# Hydrogen_Rocket_BK.net
KiCad netlist of a schematic drawn in EasyEDA
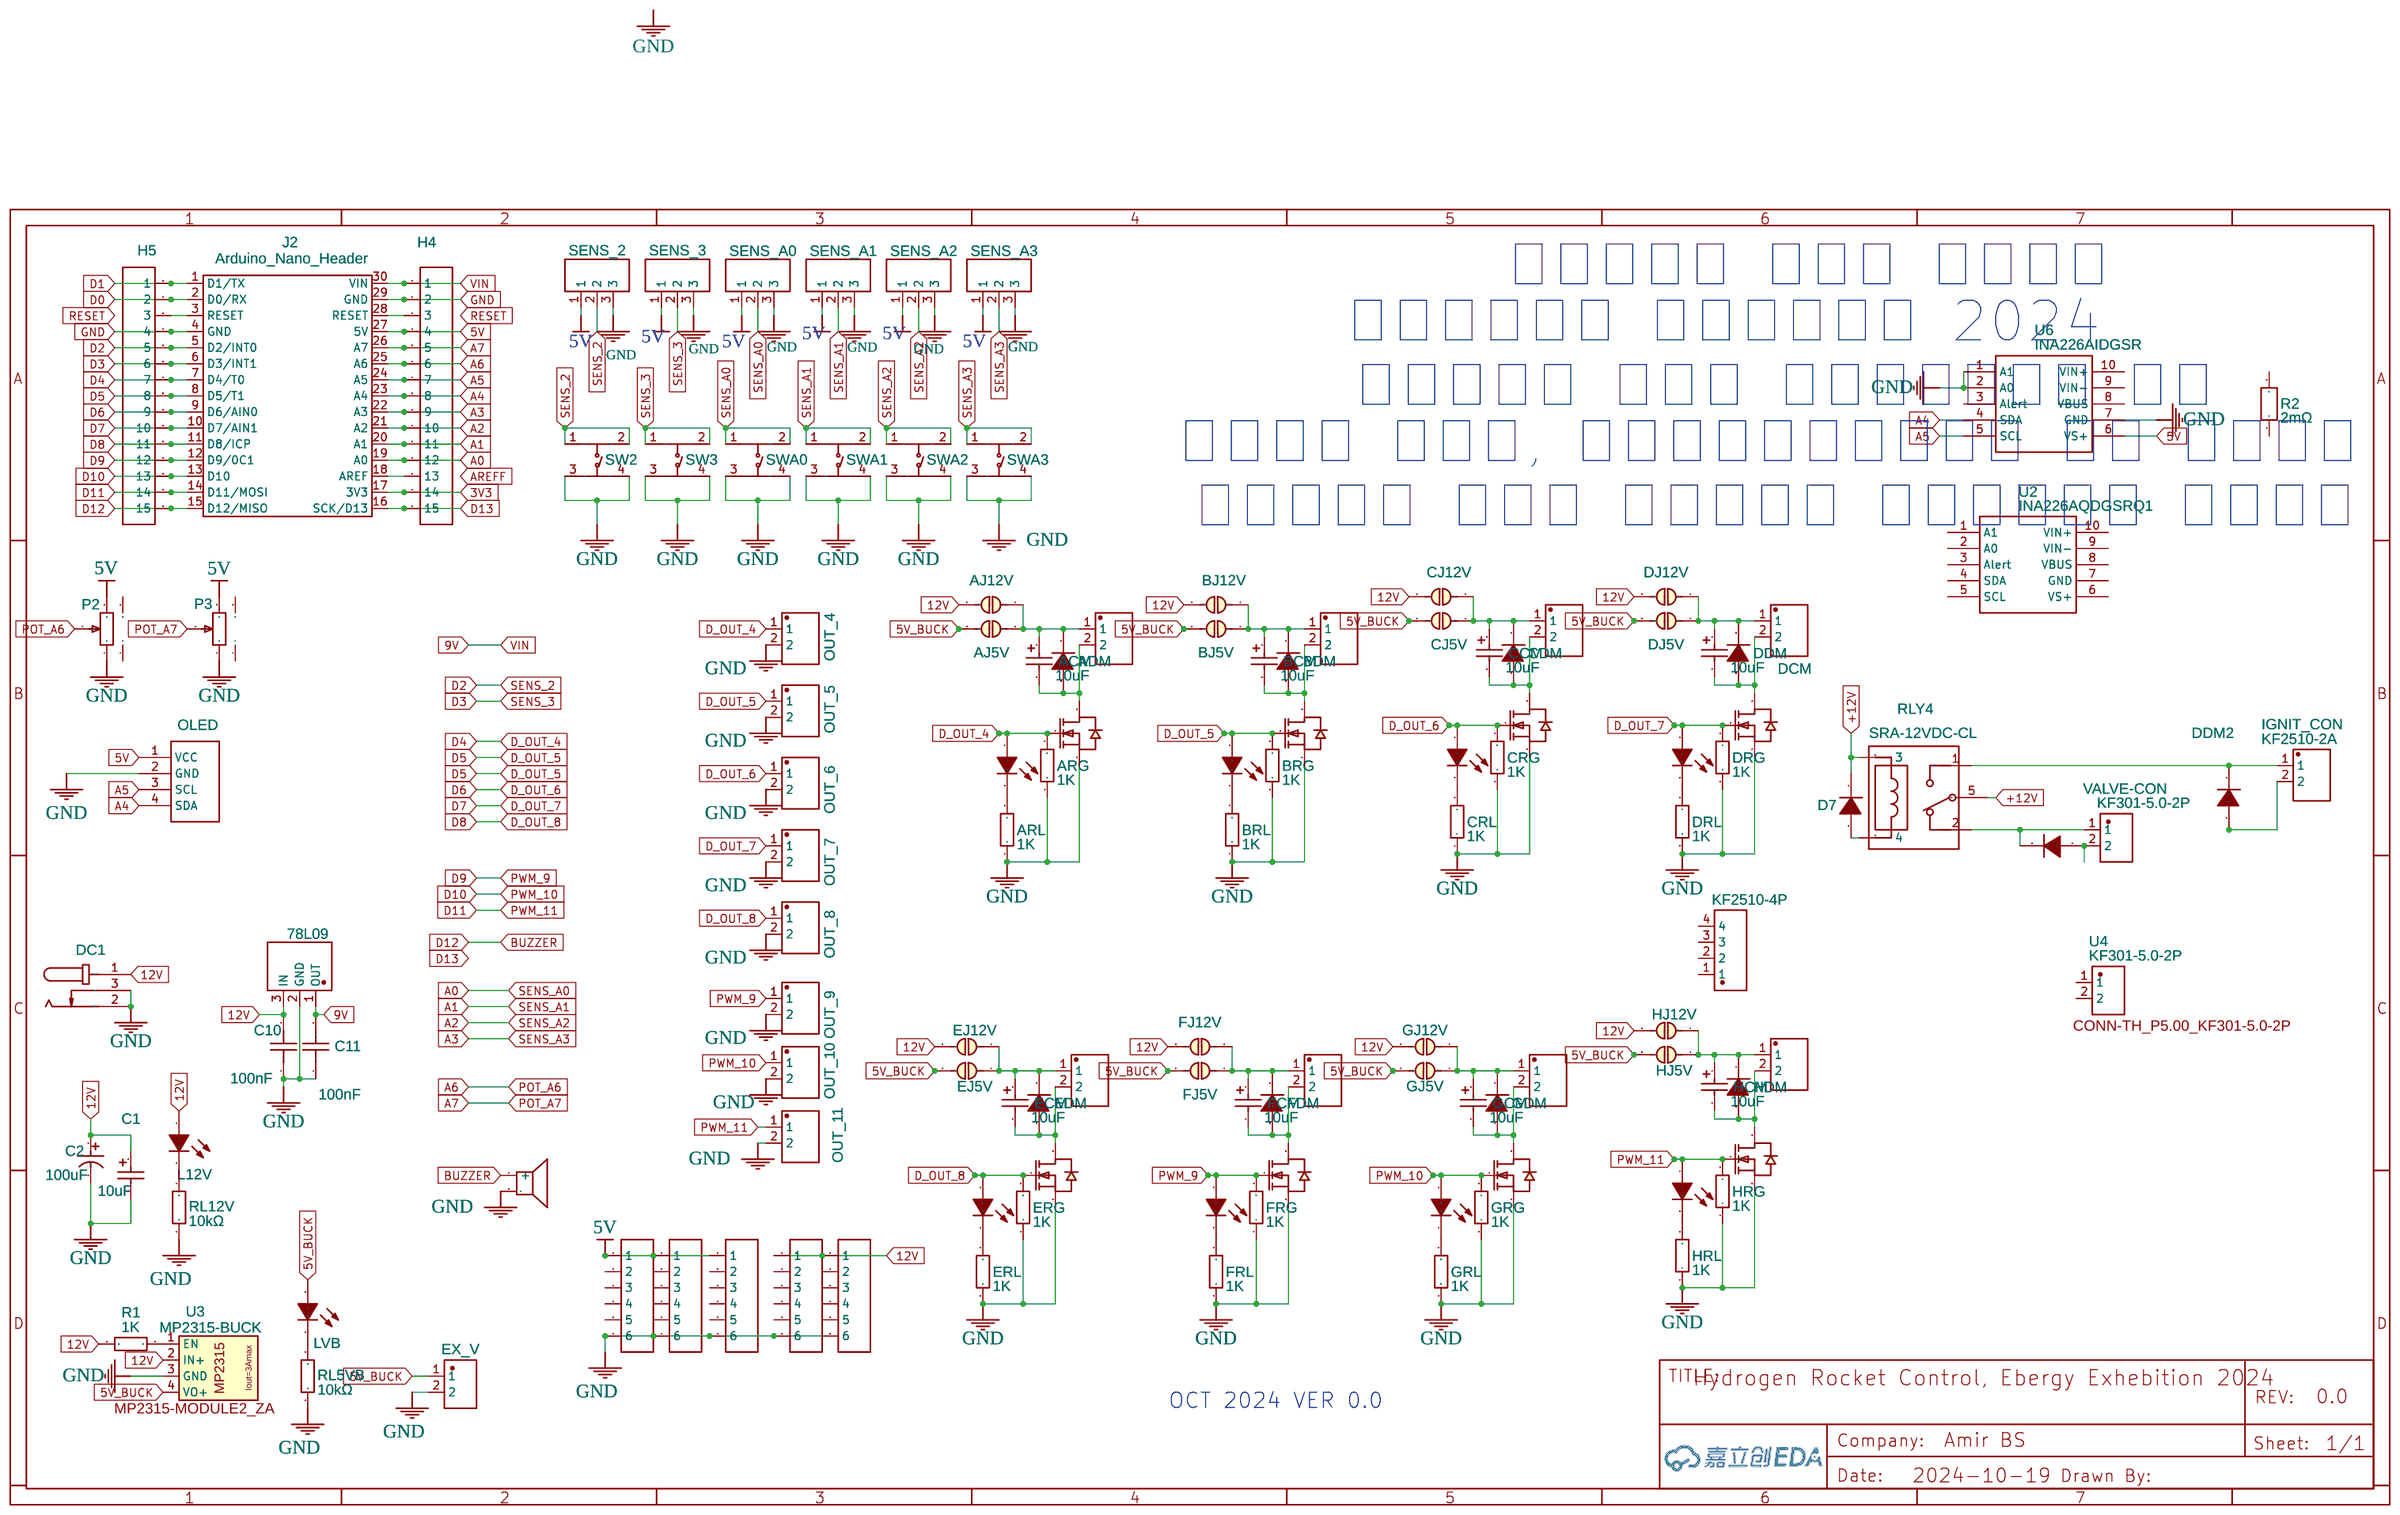
[diagram p0: schematic sheet]

(export (version "E")
  (design (tool "Eeschema 10.0.6"))
  (components
    (comp (ref "ACM") (value "10uF") (libsource (lib "") (part "TAJA106K016RNJ")))
    (comp (ref "ACON")
      (value "KF2510-2A")
      (fields (field (name "Manufacturer") "BOOMELE"))
      (libsource (lib "") (part "KF2510-2A_7"))
    )
    (comp (ref "ADM")
      (value "1N4007")
      (fields (field (name "Manufacturer Part") "1N4007F") (field (name "Manufacturer") "SK"))
      (libsource (lib "") (part "1N4007F_4"))
    )
    (comp (ref "AJ5V") (value "JUMPER-SMT_2") (libsource (lib "") (part "JUMPER-SMT_2_6")))
    (comp (ref "AJ12V") (value "JUMPER-SMT_2") (libsource (lib "") (part "JUMPER-SMT_2_8")))
    (comp (ref "ALD")
      (value "LED")
      (fields
        (field (name "Manufacturer Part") "19-217/BHC-ZL1M2RY/3T")
        (field (name "Manufacturer") "EVERLIGHT")
      )
      (libsource (lib "") (part "19-217/BHC-ZL1M2RY/3T_4"))
    )
    (comp (ref "AQ")
      (value "Q")
      (fields (field (name "Manufacturer Part") "AO3400") (field (name "Manufacturer") "ElecSuper(静芯微）"))
      (libsource (lib "") (part "JSM2302_1"))
    )
    (comp (ref "ARG")
      (value "1K")
      (fields (field (name "Manufacturer Part") "0603WAF1001T5E") (field (name "Manufacturer") "UniOhm"))
      (libsource (lib "") (part "0603WAF1001T5E_5"))
    )
    (comp (ref "ARL")
      (value "1K")
      (fields (field (name "Manufacturer Part") "0603WAF1001T5E") (field (name "Manufacturer") "UniOhm"))
      (libsource (lib "") (part "0603WAF1001T5E_1"))
    )
    (comp (ref "BCM") (value "10uF") (libsource (lib "") (part "TAJA106K016RNJ_1")))
    (comp (ref "BCON")
      (value "KF2510-2A")
      (fields (field (name "Manufacturer") "BOOMELE"))
      (libsource (lib "") (part "KF2510-2A_3"))
    )
    (comp (ref "BDM")
      (value "1N4007")
      (fields (field (name "Manufacturer Part") "1N4007F") (field (name "Manufacturer") "SK"))
      (libsource (lib "") (part "1N4007F_8"))
    )
    (comp (ref "BJ5V") (value "JUMPER-SMT_2") (libsource (lib "") (part "JUMPER-SMT_2_5")))
    (comp (ref "BJ12V") (value "JUMPER-SMT_2") (libsource (lib "") (part "JUMPER-SMT_2_1")))
    (comp (ref "BLD")
      (value "LED")
      (fields
        (field (name "Manufacturer Part") "19-217/BHC-ZL1M2RY/3T")
        (field (name "Manufacturer") "EVERLIGHT")
      )
      (libsource (lib "") (part "19-217/BHC-ZL1M2RY/3T_9"))
    )
    (comp (ref "BQ")
      (value "Q")
      (fields (field (name "Manufacturer Part") "AO3400") (field (name "Manufacturer") "ElecSuper(静芯微）"))
      (libsource (lib "") (part "JSM2302_3"))
    )
    (comp (ref "BRG")
      (value "1K")
      (fields (field (name "Manufacturer Part") "0603WAF1001T5E") (field (name "Manufacturer") "UniOhm"))
      (libsource (lib "") (part "0603WAF1001T5E_11"))
    )
    (comp (ref "BRL")
      (value "1K")
      (fields (field (name "Manufacturer Part") "0603WAF1001T5E") (field (name "Manufacturer") "UniOhm"))
      (libsource (lib "") (part "0603WAF1001T5E_10"))
    )
    (comp (ref "BUZZER1") (value "BUZZER-12X9") (libsource (lib "") (part "BUZZER-12X9")))
    (comp (ref "C1")
      (value "10uF")
      (fields (field (name "Manufacturer") "Kyocera AVX"))
      (libsource (lib "") (part "TAJA106K016RNJ_5"))
    )
    (comp (ref "C2")
      (value "100uF")
      (fields (field (name "Manufacturer") "CX(承兴)"))
      (libsource (lib "") (part "100uF 35V 6.3*11"))
    )
    (comp (ref "C10") (value "100nF") (libsource (lib "") (part "CC0603KRX7R9BB104")))
    (comp (ref "C11") (value "100nF") (libsource (lib "") (part "CC0603KRX7R9BB104")))
    (comp (ref "CCM") (value "10uF") (libsource (lib "") (part "TAJA106K016RNJ_2")))
    (comp (ref "CCON")
      (value "KF2510-2A")
      (fields (field (name "Manufacturer") "BOOMELE"))
      (libsource (lib "") (part "KF2510-2A_6"))
    )
    (comp (ref "CDM")
      (value "1N4007")
      (fields (field (name "Manufacturer Part") "1N4007F") (field (name "Manufacturer") "SK"))
      (libsource (lib "") (part "1N4007F"))
    )
    (comp (ref "CJ5V") (value "JUMPER-SMT_2") (libsource (lib "") (part "JUMPER-SMT_2_14")))
    (comp (ref "CJ12V") (value "JUMPER-SMT_2") (libsource (lib "") (part "JUMPER-SMT_2_9")))
    (comp (ref "CLD")
      (value "LED")
      (fields
        (field (name "Manufacturer Part") "19-217/BHC-ZL1M2RY/3T")
        (field (name "Manufacturer") "EVERLIGHT")
      )
      (libsource (lib "") (part "19-217/BHC-ZL1M2RY/3T_3"))
    )
    (comp (ref "CQ")
      (value "Q")
      (fields (field (name "Manufacturer Part") "AO3400") (field (name "Manufacturer") "ElecSuper(静芯微）"))
      (libsource (lib "") (part "JSM2302_5"))
    )
    (comp (ref "CRG")
      (value "1K")
      (fields (field (name "Manufacturer Part") "0603WAF1001T5E") (field (name "Manufacturer") "UniOhm"))
      (libsource (lib "") (part "0603WAF1001T5E_15"))
    )
    (comp (ref "CRL")
      (value "1K")
      (fields (field (name "Manufacturer Part") "0603WAF1001T5E") (field (name "Manufacturer") "UniOhm"))
      (libsource (lib "") (part "0603WAF1001T5E_12"))
    )
    (comp (ref "D7")
      (value "M7_C95872")
      (fields (field (name "Manufacturer") "MDD"))
      (libsource (lib "") (part "M7_C95872"))
    )
    (comp (ref "DC1")
      (value "DC")
      (fields (field (name "Manufacturer Part") "DC005-2.0MM") (field (name "Manufacturer") "SOFNG"))
      (libsource (lib "") (part "DC005-2.0MM"))
    )
    (comp (ref "DCM") (value "10uF") (libsource (lib "") (part "TAJA106K016RNJ_4")))
    (comp (ref "DCON")
      (value "KF2510-2A")
      (fields (field (name "Manufacturer") "BOOMELE"))
      (libsource (lib "") (part "KF2510-2A_2"))
    )
    (comp (ref "DDM")
      (value "1N4007")
      (fields (field (name "Manufacturer Part") "1N4007F") (field (name "Manufacturer") "SK"))
      (libsource (lib "") (part "1N4007F_2"))
    )
    (comp (ref "DDM1")
      (value "1N4007")
      (fields (field (name "Manufacturer Part") "1N4007F") (field (name "Manufacturer") "SK"))
      (libsource (lib "") (part "1N4007F_3"))
    )
    (comp (ref "DDM2")
      (value "1N4007")
      (fields (field (name "Manufacturer Part") "1N4007F") (field (name "Manufacturer") "SK"))
      (libsource (lib "") (part "1N4007F_2"))
    )
    (comp (ref "DJ5V") (value "JUMPER-SMT_2") (libsource (lib "") (part "JUMPER-SMT_2_10")))
    (comp (ref "DJ12V") (value "JUMPER-SMT_2") (libsource (lib "") (part "JUMPER-SMT_2_7")))
    (comp (ref "DLD")
      (value "LED")
      (fields
        (field (name "Manufacturer Part") "19-217/BHC-ZL1M2RY/3T")
        (field (name "Manufacturer") "EVERLIGHT")
      )
      (libsource (lib "") (part "19-217/BHC-ZL1M2RY/3T_7"))
    )
    (comp (ref "DQ")
      (value "Q")
      (fields (field (name "Manufacturer Part") "AO3400") (field (name "Manufacturer") "ElecSuper(静芯微）"))
      (libsource (lib "") (part "JSM2302_6"))
    )
    (comp (ref "DRG")
      (value "1K")
      (fields (field (name "Manufacturer Part") "0603WAF1001T5E") (field (name "Manufacturer") "UniOhm"))
      (libsource (lib "") (part "0603WAF1001T5E_4"))
    )
    (comp (ref "DRL")
      (value "1K")
      (fields (field (name "Manufacturer Part") "0603WAF1001T5E") (field (name "Manufacturer") "UniOhm"))
      (libsource (lib "") (part "0603WAF1001T5E_2"))
    )
    (comp (ref "ECM") (value "10uF") (libsource (lib "") (part "TAJA106K016RNJ_7")))
    (comp (ref "ECON")
      (value "KF2510-2A")
      (fields (field (name "Manufacturer") "BOOMELE"))
      (libsource (lib "") (part "KF2510-2A_5"))
    )
    (comp (ref "EDM")
      (value "1N4007")
      (fields (field (name "Manufacturer Part") "1N4007F") (field (name "Manufacturer") "SK"))
      (libsource (lib "") (part "1N4007F_5"))
    )
    (comp (ref "EJ5V") (value "JUMPER-SMT_2") (libsource (lib "") (part "JUMPER-SMT_2_2")))
    (comp (ref "EJ12V") (value "JUMPER-SMT_2") (libsource (lib "") (part "JUMPER-SMT_2_13")))
    (comp (ref "ELD")
      (value "LED")
      (fields
        (field (name "Manufacturer Part") "19-217/BHC-ZL1M2RY/3T")
        (field (name "Manufacturer") "EVERLIGHT")
      )
      (libsource (lib "") (part "19-217/BHC-ZL1M2RY/3T_6"))
    )
    (comp (ref "EQ")
      (value "Q")
      (fields (field (name "Manufacturer Part") "AO3400") (field (name "Manufacturer") "ElecSuper(静芯微）"))
      (libsource (lib "") (part "JSM2302_2"))
    )
    (comp (ref "ERG")
      (value "1K")
      (fields (field (name "Manufacturer Part") "0603WAF1001T5E") (field (name "Manufacturer") "UniOhm"))
      (libsource (lib "") (part "0603WAF1001T5E_8"))
    )
    (comp (ref "ERL")
      (value "1K")
      (fields (field (name "Manufacturer Part") "0603WAF1001T5E") (field (name "Manufacturer") "UniOhm"))
      (libsource (lib "") (part "0603WAF1001T5E_3"))
    )
    (comp (ref "EX_V")
      (value "EX_V")
      (fields (field (name "Manufacturer") "KANGNEX(康奈克斯电气)"))
      (libsource (lib "") (part "WJ306V-5.0-2P-14-00A"))
    )
    (comp (ref "FCM") (value "10uF") (libsource (lib "") (part "TAJA106K016RNJ_6")))
    (comp (ref "FCON")
      (value "KF2510-2A")
      (fields (field (name "Manufacturer") "BOOMELE"))
      (libsource (lib "") (part "KF2510-2A_1"))
    )
    (comp (ref "FDM")
      (value "1N4007")
      (fields (field (name "Manufacturer Part") "1N4007F") (field (name "Manufacturer") "SK"))
      (libsource (lib "") (part "1N4007F_6"))
    )
    (comp (ref "FJ5V") (value "JUMPER-SMT_2") (libsource (lib "") (part "JUMPER-SMT_2_11")))
    (comp (ref "FJ12V") (value "JUMPER-SMT_2") (libsource (lib "") (part "JUMPER-SMT_2_4")))
    (comp (ref "FLD")
      (value "LED")
      (fields
        (field (name "Manufacturer Part") "19-217/BHC-ZL1M2RY/3T")
        (field (name "Manufacturer") "EVERLIGHT")
      )
      (libsource (lib "") (part "19-217/BHC-ZL1M2RY/3T"))
    )
    (comp (ref "FQ")
      (value "Q")
      (fields (field (name "Manufacturer Part") "AO3400") (field (name "Manufacturer") "ElecSuper(静芯微）"))
      (libsource (lib "") (part "JSM2302_4"))
    )
    (comp (ref "FRG")
      (value "1K")
      (fields (field (name "Manufacturer Part") "0603WAF1001T5E") (field (name "Manufacturer") "UniOhm"))
      (libsource (lib "") (part "0603WAF1001T5E_14"))
    )
    (comp (ref "FRL")
      (value "1K")
      (fields (field (name "Manufacturer Part") "0603WAF1001T5E") (field (name "Manufacturer") "UniOhm"))
      (libsource (lib "") (part "0603WAF1001T5E_6"))
    )
    (comp (ref "GCM") (value "10uF") (libsource (lib "") (part "TAJA106K016RNJ_8")))
    (comp (ref "GCON")
      (value "KF2510-2A")
      (fields (field (name "Manufacturer") "BOOMELE"))
      (libsource (lib "") (part "KF2510-2A_9"))
    )
    (comp (ref "GDM")
      (value "1N4007")
      (fields (field (name "Manufacturer Part") "1N4007F") (field (name "Manufacturer") "SK"))
      (libsource (lib "") (part "1N4007F_7"))
    )
    (comp (ref "GJ5V") (value "JUMPER-SMT_2") (libsource (lib "") (part "JUMPER-SMT_2_15")))
    (comp (ref "GJ12V") (value "JUMPER-SMT_2") (libsource (lib "") (part "JUMPER-SMT_2_3")))
    (comp (ref "GLD")
      (value "LED")
      (fields
        (field (name "Manufacturer Part") "19-217/BHC-ZL1M2RY/3T")
        (field (name "Manufacturer") "EVERLIGHT")
      )
      (libsource (lib "") (part "19-217/BHC-ZL1M2RY/3T_5"))
    )
    (comp (ref "GQ")
      (value "Q")
      (fields (field (name "Manufacturer Part") "AO3400") (field (name "Manufacturer") "ElecSuper(静芯微）"))
      (libsource (lib "") (part "JSM2302"))
    )
    (comp (ref "GRG")
      (value "1K")
      (fields (field (name "Manufacturer Part") "0603WAF1001T5E") (field (name "Manufacturer") "UniOhm"))
      (libsource (lib "") (part "0603WAF1001T5E_13"))
    )
    (comp (ref "GRL")
      (value "1K")
      (fields (field (name "Manufacturer Part") "0603WAF1001T5E") (field (name "Manufacturer") "UniOhm"))
      (libsource (lib "") (part "0603WAF1001T5E_9"))
    )
    (comp (ref "H1") (value "HDR-F-2.54_1x6") (libsource (lib "") (part "HDR-F-2.54_1x6")))
    (comp (ref "H2") (value "HDR-F-2.54_1x6") (libsource (lib "") (part "HDR-F-2.54_1x6")))
    (comp (ref "H3") (value "HDR-F-2.54_1x6") (libsource (lib "") (part "HDR-F-2.54_1x6")))
    (comp (ref "H4") (value "HDR-F-2.54_1x15") (libsource (lib "") (part "HDR-F-2.54_1x15")))
    (comp (ref "H5") (value "HDR-F-2.54_1x15") (libsource (lib "") (part "HDR-F-2.54_1x15_1")))
    (comp (ref "H6") (value "HDR-F-2.54_1x6") (libsource (lib "") (part "HDR-F-2.54_1x6")))
    (comp (ref "H11") (value "HDR-F-2.54_1x6") (libsource (lib "") (part "HDR-F-2.54_1x6")))
    (comp (ref "HCM") (value "10uF") (libsource (lib "") (part "TAJA106K016RNJ_3")))
    (comp (ref "HCON")
      (value "KF2510-2A")
      (fields (field (name "Manufacturer") "BOOMELE"))
      (libsource (lib "") (part "KF2510-2A_8"))
    )
    (comp (ref "HDM")
      (value "1N4007")
      (fields (field (name "Manufacturer Part") "1N4007F") (field (name "Manufacturer") "SK"))
      (libsource (lib "") (part "1N4007F_1"))
    )
    (comp (ref "HJ5V") (value "JUMPER-SMT_2") (libsource (lib "") (part "JUMPER-SMT_2")))
    (comp (ref "HJ12V") (value "JUMPER-SMT_2") (libsource (lib "") (part "JUMPER-SMT_2_12")))
    (comp (ref "HLD")
      (value "LED")
      (fields
        (field (name "Manufacturer Part") "19-217/BHC-ZL1M2RY/3T")
        (field (name "Manufacturer") "EVERLIGHT")
      )
      (libsource (lib "") (part "19-217/BHC-ZL1M2RY/3T_8"))
    )
    (comp (ref "HQ")
      (value "Q")
      (fields (field (name "Manufacturer Part") "AO3400") (field (name "Manufacturer") "ElecSuper(静芯微）"))
      (libsource (lib "") (part "JSM2302_7"))
    )
    (comp (ref "HRG")
      (value "1K")
      (fields (field (name "Manufacturer Part") "0603WAF1001T5E") (field (name "Manufacturer") "UniOhm"))
      (libsource (lib "") (part "0603WAF1001T5E_16"))
    )
    (comp (ref "HRL")
      (value "1K")
      (fields (field (name "Manufacturer Part") "0603WAF1001T5E") (field (name "Manufacturer") "UniOhm"))
      (libsource (lib "") (part "0603WAF1001T5E_7"))
    )
    (comp (ref "IGNIT_CON")
      (value "KF2510-2A")
      (fields (field (name "Manufacturer") "BOOMELE"))
      (libsource (lib "") (part "KF2510-2A_4"))
    )
    (comp (ref "J2") (value "Arduino_Nano_Header") (libsource (lib "") (part "Arduino_Nano_Header")))
    (comp (ref "L12V")
      (value "LED")
      (fields
        (field (name "Manufacturer Part") "19-217/BHC-ZL1M2RY/3T")
        (field (name "Manufacturer") "EVERLIGHT")
      )
      (libsource (lib "") (part "19-217/BHC-ZL1M2RY/3T_1"))
    )
    (comp (ref "LVB")
      (value "LED")
      (fields
        (field (name "Manufacturer Part") "19-217/BHC-ZL1M2RY/3T")
        (field (name "Manufacturer") "EVERLIGHT")
      )
      (libsource (lib "") (part "19-217/BHC-ZL1M2RY/3T_2"))
    )
    (comp (ref "OLED")
      (value "1.3 inch OLED SSH1106 I2C 128x64 copy")
      (libsource (lib "") (part "1.3 inch OLED SSH1106 I2C 128x64 copy"))
    )
    (comp (ref "OUT_4")
      (value "KF2510-2A")
      (fields (field (name "Manufacturer") "BOOMELE"))
      (libsource (lib "") (part "KF2510-2A"))
    )
    (comp (ref "OUT_5")
      (value "KF2510-2A")
      (fields (field (name "Manufacturer") "BOOMELE"))
      (libsource (lib "") (part "KF2510-2A"))
    )
    (comp (ref "OUT_6")
      (value "KF2510-2A")
      (fields (field (name "Manufacturer") "BOOMELE"))
      (libsource (lib "") (part "KF2510-2A"))
    )
    (comp (ref "OUT_7")
      (value "KF2510-2A")
      (fields (field (name "Manufacturer") "BOOMELE"))
      (libsource (lib "") (part "KF2510-2A"))
    )
    (comp (ref "OUT_8")
      (value "KF2510-2A")
      (fields (field (name "Manufacturer") "BOOMELE"))
      (libsource (lib "") (part "KF2510-2A"))
    )
    (comp (ref "OUT_9")
      (value "KF2510-2A")
      (fields (field (name "Manufacturer") "BOOMELE"))
      (libsource (lib "") (part "KF2510-2A"))
    )
    (comp (ref "OUT_10")
      (value "KF2510-2A")
      (fields (field (name "Manufacturer") "BOOMELE"))
      (libsource (lib "") (part "KF2510-2A"))
    )
    (comp (ref "OUT_11")
      (value "KF2510-2A")
      (fields (field (name "Manufacturer") "BOOMELE"))
      (libsource (lib "") (part "KF2510-2A"))
    )
    (comp (ref "P2") (value "长柄旋转电位器") (libsource (lib "") (part "长柄旋转电位器")))
    (comp (ref "P3") (value "长柄旋转电位器") (libsource (lib "") (part "长柄旋转电位器")))
    (comp (ref "R1")
      (value "1K")
      (fields (field (name "Manufacturer Part") "0603WAF1001T5E") (field (name "Manufacturer") "UniOhm"))
      (libsource (lib "") (part "0603WAF1001T5E"))
    )
    (comp (ref "R2")
      (value "2mΩ")
      (fields
        (field (name "Manufacturer Part") "BVS-A-R002-1.0")
        (field (name "Manufacturer") "Isabellenhuette(伊萨普兰)")
      )
      (libsource (lib "") (part "BVS-A-R002-1.0"))
    )
    (comp (ref "RL5VB")
      (value "10kΩ")
      (fields
        (field (name "Manufacturer Part") "0603WAF1002T5E")
        (field (name "Manufacturer") "UNI-ROYAL(厚声)")
      )
      (libsource (lib "") (part "0603WAF1002T5E_1"))
    )
    (comp (ref "RL12V")
      (value "10kΩ")
      (fields
        (field (name "Manufacturer Part") "0603WAF1002T5E")
        (field (name "Manufacturer") "UNI-ROYAL(厚声)")
      )
      (libsource (lib "") (part "0603WAF1002T5E"))
    )
    (comp (ref "RLY4")
      (value "SRA-12VDC-CL")
      (fields (field (name "Manufacturer") "松乐"))
      (libsource (lib "") (part "SRA-12VDC-CL"))
    )
    (comp (ref "SENS_2") (value "FK2510") (libsource (lib "") (part "kf2510_3A_1")))
    (comp (ref "SENS_3") (value "FK2510") (libsource (lib "") (part "kf2510_3A_1")))
    (comp (ref "SENS_A0") (value "FK2510") (libsource (lib "") (part "kf2510_3A")))
    (comp (ref "SENS_A1") (value "FK2510") (libsource (lib "") (part "kf2510_3A")))
    (comp (ref "SENS_A2") (value "FK2510") (libsource (lib "") (part "kf2510_3A")))
    (comp (ref "SENS_A3") (value "FK2510") (libsource (lib "") (part "kf2510_3A")))
    (comp (ref "SW2")
      (value "TC-6610-7-160G")
      (fields (field (name "Manufacturer") "HCTL(华灿天禄)"))
      (libsource (lib "") (part "TC-6610-7-160G_1"))
    )
    (comp (ref "SW3")
      (value "TC-6610-7-160G")
      (fields (field (name "Manufacturer") "HCTL(华灿天禄)"))
      (libsource (lib "") (part "TC-6610-7-160G_1"))
    )
    (comp (ref "SWA0")
      (value "TC-6610-7-160G")
      (fields (field (name "Manufacturer") "HCTL(华灿天禄)"))
      (libsource (lib "") (part "TC-6610-7-160G"))
    )
    (comp (ref "SWA1")
      (value "TC-6610-7-160G")
      (fields (field (name "Manufacturer") "HCTL(华灿天禄)"))
      (libsource (lib "") (part "TC-6610-7-160G"))
    )
    (comp (ref "SWA2")
      (value "TC-6610-7-160G")
      (fields (field (name "Manufacturer") "HCTL(华灿天禄)"))
      (libsource (lib "") (part "TC-6610-7-160G"))
    )
    (comp (ref "SWA3")
      (value "TC-6610-7-160G")
      (fields (field (name "Manufacturer") "HCTL(华灿天禄)"))
      (libsource (lib "") (part "TC-6610-7-160G"))
    )
    (comp (ref "U1") (value "KF2510-4P") (libsource (lib "") (part "KF2510-4P")))
    (comp (ref "U2")
      (value "INA226AQDGSRQ1")
      (fields (field (name "Manufacturer") "TI(德州仪器)"))
      (libsource (lib "") (part "INA226AQDGSRQ1"))
    )
    (comp (ref "U3") (value "MP2315-BUCK") (libsource (lib "") (part "MP2315-BUCK")))
    (comp (ref "U4")
      (value "KF301-5.0-2P")
      (fields (field (name "Manufacturer") "KEFA(科发)"))
      (libsource (lib "") (part "KF301-5.0-2P"))
    )
    (comp (ref "U5")
      (value "78L09")
      (fields (field (name "Manufacturer") "CBI(创基)"))
      (libsource (lib "") (part "78L09U 78L09"))
    )
    (comp (ref "U6")
      (value "INA226AIDGSR")
      (fields (field (name "Manufacturer") "TI(德州仪器)"))
      (libsource (lib "") (part "INA226AIDGSR"))
    )
    (comp (ref "VALVE-CON")
      (value "KF301-5.0-2P")
      (fields (field (name "Manufacturer") "KEFA(科发)"))
      (libsource (lib "") (part "KF301-5.0-2P_1"))
    )
  )
  (nets
    (net (code "1") (name "+12V") (class "Default")
      (node (ref "D7") (pin "1") (pinfunction "K_1") (pintype "unspecified"))
      (node (ref "RLY4") (pin "3") (pinfunction "3_3") (pintype "unspecified"))
      (node (ref "RLY4") (pin "5") (pinfunction "5_5") (pintype "unspecified"))
    )
    (net (code "2") (name "3V3") (class "Default")
      (node (ref "H4") (pin "14") (pinfunction "14_14") (pintype "unspecified"))
      (node (ref "J2") (pin "17") (pinfunction "3V3_17") (pintype "unspecified"))
    )
    (net (code "3") (name "5V") (class "Default")
      (node (ref "H1") (pin "1") (pinfunction "1_1") (pintype "input"))
      (node (ref "H2") (pin "1") (pinfunction "1_1") (pintype "input"))
      (node (ref "H3") (pin "1") (pinfunction "1_1") (pintype "input"))
      (node (ref "H4") (pin "4") (pinfunction "4_4") (pintype "unspecified"))
      (node (ref "J2") (pin "27") (pinfunction "5V_27") (pintype "unspecified"))
      (node (ref "OLED") (pin "1") (pinfunction "VCC_1") (pintype "passive"))
      (node (ref "P2") (pin "3") (pinfunction "3_3") (pintype "input"))
      (node (ref "P3") (pin "3") (pinfunction "3_3") (pintype "input"))
      (node (ref "SENS_2") (pin "1") (pinfunction "1_1") (pintype "unspecified"))
      (node (ref "SENS_3") (pin "1") (pinfunction "1_1") (pintype "unspecified"))
      (node (ref "SENS_A0") (pin "1") (pinfunction "1_1") (pintype "unspecified"))
      (node (ref "SENS_A1") (pin "1") (pinfunction "1_1") (pintype "unspecified"))
      (node (ref "SENS_A2") (pin "1") (pinfunction "1_1") (pintype "unspecified"))
      (node (ref "SENS_A3") (pin "1") (pinfunction "1_1") (pintype "unspecified"))
      (node (ref "U6") (pin "6") (pinfunction "VS+_6") (pintype "unspecified"))
    )
    (net (code "4") (name "5V_BUCK") (class "Default")
      (node (ref "AJ5V") (pin "2") (pinfunction "2_2") (pintype "bidirectional"))
      (node (ref "BJ5V") (pin "2") (pinfunction "2_2") (pintype "bidirectional"))
      (node (ref "CJ5V") (pin "2") (pinfunction "2_2") (pintype "bidirectional"))
      (node (ref "DJ5V") (pin "2") (pinfunction "2_2") (pintype "bidirectional"))
      (node (ref "EJ5V") (pin "2") (pinfunction "2_2") (pintype "bidirectional"))
      (node (ref "EX_V") (pin "1") (pinfunction "1_1") (pintype "unspecified"))
      (node (ref "FJ5V") (pin "2") (pinfunction "2_2") (pintype "bidirectional"))
      (node (ref "GJ5V") (pin "2") (pinfunction "2_2") (pintype "bidirectional"))
      (node (ref "HJ5V") (pin "2") (pinfunction "2_2") (pintype "bidirectional"))
      (node (ref "LVB") (pin "1") (pinfunction "A_1") (pintype "input"))
      (node (ref "U3") (pin "4") (pinfunction "VO+_4") (pintype "unspecified"))
    )
    (net (code "5") (name "9V") (class "Default")
      (node (ref "C11") (pin "2") (pinfunction "2_2") (pintype "unspecified"))
      (node (ref "H4") (pin "1") (pinfunction "1_1") (pintype "unspecified"))
      (node (ref "J2") (pin "30") (pinfunction "VIN_30") (pintype "unspecified"))
      (node (ref "U5") (pin "1") (pinfunction "OUT_1") (pintype "unspecified"))
    )
    (net (code "6") (name "12V") (class "Default")
      (node (ref "AJ12V") (pin "2") (pinfunction "2_2") (pintype "bidirectional"))
      (node (ref "BJ12V") (pin "2") (pinfunction "2_2") (pintype "bidirectional"))
      (node (ref "C1") (pin "1") (pinfunction "1_1") (pintype "input"))
      (node (ref "C10") (pin "2") (pinfunction "2_2") (pintype "unspecified"))
      (node (ref "C2") (pin "1") (pinfunction "1_1") (pintype "input"))
      (node (ref "CJ12V") (pin "2") (pinfunction "2_2") (pintype "bidirectional"))
      (node (ref "DC1") (pin "1") (pinfunction "1_1") (pintype "unspecified"))
      (node (ref "DJ12V") (pin "2") (pinfunction "2_2") (pintype "bidirectional"))
      (node (ref "EJ12V") (pin "2") (pinfunction "2_2") (pintype "bidirectional"))
      (node (ref "FJ12V") (pin "2") (pinfunction "2_2") (pintype "bidirectional"))
      (node (ref "GJ12V") (pin "2") (pinfunction "2_2") (pintype "bidirectional"))
      (node (ref "H11") (pin "1") (pinfunction "1_1") (pintype "input"))
      (node (ref "H6") (pin "1") (pinfunction "1_1") (pintype "input"))
      (node (ref "HJ12V") (pin "2") (pinfunction "2_2") (pintype "bidirectional"))
      (node (ref "L12V") (pin "1") (pinfunction "A_1") (pintype "input"))
      (node (ref "R1") (pin "2") (pinfunction "2_2") (pintype "input"))
      (node (ref "U3") (pin "2") (pinfunction "IN+_2") (pintype "unspecified"))
      (node (ref "U5") (pin "3") (pinfunction "IN_3") (pintype "unspecified"))
    )
    (net (code "7") (name "A0") (class "Default")
      (node (ref "H4") (pin "12") (pinfunction "12_12") (pintype "unspecified"))
      (node (ref "J2") (pin "19") (pinfunction "A0_19") (pintype "unspecified"))
      (node (ref "SENS_A0") (pin "2") (pinfunction "2_2") (pintype "unspecified"))
      (node (ref "SWA0") (pin "1") (pinfunction "1_1") (pintype "unspecified"))
      (node (ref "SWA0") (pin "2") (pinfunction "2_2") (pintype "unspecified"))
    )
    (net (code "8") (name "A1") (class "Default")
      (node (ref "H4") (pin "11") (pinfunction "11_11") (pintype "unspecified"))
      (node (ref "J2") (pin "20") (pinfunction "A1_20") (pintype "unspecified"))
      (node (ref "SENS_A1") (pin "2") (pinfunction "2_2") (pintype "unspecified"))
      (node (ref "SWA1") (pin "1") (pinfunction "1_1") (pintype "unspecified"))
      (node (ref "SWA1") (pin "2") (pinfunction "2_2") (pintype "unspecified"))
    )
    (net (code "9") (name "A2") (class "Default")
      (node (ref "H4") (pin "10") (pinfunction "10_10") (pintype "unspecified"))
      (node (ref "J2") (pin "21") (pinfunction "A2_21") (pintype "unspecified"))
      (node (ref "SENS_A2") (pin "2") (pinfunction "2_2") (pintype "unspecified"))
      (node (ref "SWA2") (pin "1") (pinfunction "1_1") (pintype "unspecified"))
      (node (ref "SWA2") (pin "2") (pinfunction "2_2") (pintype "unspecified"))
    )
    (net (code "10") (name "A3") (class "Default")
      (node (ref "H4") (pin "9") (pinfunction "9_9") (pintype "unspecified"))
      (node (ref "J2") (pin "22") (pinfunction "A3_22") (pintype "unspecified"))
      (node (ref "SENS_A3") (pin "2") (pinfunction "2_2") (pintype "unspecified"))
      (node (ref "SWA3") (pin "1") (pinfunction "1_1") (pintype "unspecified"))
      (node (ref "SWA3") (pin "2") (pinfunction "2_2") (pintype "unspecified"))
    )
    (net (code "11") (name "A4") (class "Default")
      (node (ref "H4") (pin "8") (pinfunction "8_8") (pintype "unspecified"))
      (node (ref "J2") (pin "23") (pinfunction "A4_23") (pintype "unspecified"))
      (node (ref "OLED") (pin "4") (pinfunction "SDA_4") (pintype "bidirectional"))
      (node (ref "U6") (pin "4") (pinfunction "SDA_4") (pintype "unspecified"))
    )
    (net (code "12") (name "A5") (class "Default")
      (node (ref "H4") (pin "7") (pinfunction "7_7") (pintype "unspecified"))
      (node (ref "J2") (pin "24") (pinfunction "A5_24") (pintype "unspecified"))
      (node (ref "OLED") (pin "3") (pinfunction "SCL_3") (pintype "bidirectional"))
      (node (ref "U6") (pin "5") (pinfunction "SCL_5") (pintype "unspecified"))
    )
    (net (code "13") (name "A6") (class "Default")
      (node (ref "H4") (pin "6") (pinfunction "6_6") (pintype "unspecified"))
      (node (ref "J2") (pin "25") (pinfunction "A6_25") (pintype "unspecified"))
      (node (ref "P2") (pin "2") (pinfunction "2_2") (pintype "input"))
    )
    (net (code "14") (name "A7") (class "Default")
      (node (ref "H4") (pin "5") (pinfunction "5_5") (pintype "unspecified"))
      (node (ref "J2") (pin "26") (pinfunction "A7_26") (pintype "unspecified"))
      (node (ref "P3") (pin "2") (pinfunction "2_2") (pintype "input"))
    )
    (net (code "16") (name "BUZZER") (class "Default")
      (node (ref "BUZZER1") (pin "1") (pinfunction "+_1") (pintype "unspecified"))
      (node (ref "H5") (pin "15") (pinfunction "15_15") (pintype "unspecified"))
      (node (ref "J2") (pin "15") (pinfunction "D12/MISO_15") (pintype "unspecified"))
    )
    (net (code "17") (name "D0") (class "Default")
      (node (ref "H5") (pin "2") (pinfunction "2_2") (pintype "unspecified"))
      (node (ref "J2") (pin "2") (pinfunction "D0/RX_2") (pintype "unspecified"))
    )
    (net (code "18") (name "D1") (class "Default")
      (node (ref "H5") (pin "1") (pinfunction "1_1") (pintype "unspecified"))
      (node (ref "J2") (pin "1") (pinfunction "D1/TX_1") (pintype "unspecified"))
    )
    (net (code "19") (name "D2") (class "Default")
      (node (ref "H5") (pin "5") (pinfunction "5_5") (pintype "unspecified"))
      (node (ref "J2") (pin "5") (pinfunction "D2/INT0_5") (pintype "unspecified"))
      (node (ref "SENS_2") (pin "2") (pinfunction "2_2") (pintype "unspecified"))
      (node (ref "SW2") (pin "1") (pinfunction "1_1") (pintype "unspecified"))
      (node (ref "SW2") (pin "2") (pinfunction "2_2") (pintype "unspecified"))
    )
    (net (code "20") (name "D3") (class "Default")
      (node (ref "H5") (pin "6") (pinfunction "6_6") (pintype "unspecified"))
      (node (ref "J2") (pin "6") (pinfunction "D3/INT1_6") (pintype "unspecified"))
      (node (ref "SENS_3") (pin "2") (pinfunction "2_2") (pintype "unspecified"))
      (node (ref "SW3") (pin "1") (pinfunction "1_1") (pintype "unspecified"))
      (node (ref "SW3") (pin "2") (pinfunction "2_2") (pintype "unspecified"))
    )
    (net (code "21") (name "D4") (class "Default")
      (node (ref "ALD") (pin "1") (pinfunction "A_1") (pintype "input"))
      (node (ref "AQ") (pin "1") (pinfunction "G_1") (pintype "unspecified"))
      (node (ref "ARG") (pin "2") (pinfunction "2_2") (pintype "input"))
      (node (ref "H5") (pin "7") (pinfunction "7_7") (pintype "unspecified"))
      (node (ref "J2") (pin "7") (pinfunction "D4/T0_7") (pintype "unspecified"))
      (node (ref "OUT_4") (pin "1") (pinfunction "1_1") (pintype "unspecified"))
    )
    (net (code "22") (name "D5") (class "Default")
      (node (ref "BLD") (pin "1") (pinfunction "A_1") (pintype "input"))
      (node (ref "BQ") (pin "1") (pinfunction "G_1") (pintype "unspecified"))
      (node (ref "BRG") (pin "2") (pinfunction "2_2") (pintype "input"))
      (node (ref "H5") (pin "8") (pinfunction "8_8") (pintype "unspecified"))
      (node (ref "J2") (pin "8") (pinfunction "D5/T1_8") (pintype "unspecified"))
      (node (ref "OUT_5") (pin "1") (pinfunction "1_1") (pintype "unspecified"))
    )
    (net (code "23") (name "D6") (class "Default")
      (node (ref "CLD") (pin "1") (pinfunction "A_1") (pintype "input"))
      (node (ref "CQ") (pin "1") (pinfunction "G_1") (pintype "unspecified"))
      (node (ref "CRG") (pin "2") (pinfunction "2_2") (pintype "input"))
      (node (ref "H5") (pin "9") (pinfunction "9_9") (pintype "unspecified"))
      (node (ref "J2") (pin "9") (pinfunction "D6/AIN0_9") (pintype "unspecified"))
      (node (ref "OUT_6") (pin "1") (pinfunction "1_1") (pintype "unspecified"))
    )
    (net (code "24") (name "D7") (class "Default")
      (node (ref "DLD") (pin "1") (pinfunction "A_1") (pintype "input"))
      (node (ref "DQ") (pin "1") (pinfunction "G_1") (pintype "unspecified"))
      (node (ref "DRG") (pin "2") (pinfunction "2_2") (pintype "input"))
      (node (ref "H5") (pin "10") (pinfunction "10_10") (pintype "unspecified"))
      (node (ref "J2") (pin "10") (pinfunction "D7/AIN1_10") (pintype "unspecified"))
      (node (ref "OUT_7") (pin "1") (pinfunction "1_1") (pintype "unspecified"))
    )
    (net (code "25") (name "D8") (class "Default")
      (node (ref "ELD") (pin "1") (pinfunction "A_1") (pintype "input"))
      (node (ref "EQ") (pin "1") (pinfunction "G_1") (pintype "unspecified"))
      (node (ref "ERG") (pin "2") (pinfunction "2_2") (pintype "input"))
      (node (ref "H5") (pin "11") (pinfunction "11_11") (pintype "unspecified"))
      (node (ref "J2") (pin "11") (pinfunction "D8/ICP_11") (pintype "unspecified"))
      (node (ref "OUT_8") (pin "1") (pinfunction "1_1") (pintype "unspecified"))
    )
    (net (code "26") (name "D9") (class "Default")
      (node (ref "FLD") (pin "1") (pinfunction "A_1") (pintype "input"))
      (node (ref "FQ") (pin "1") (pinfunction "G_1") (pintype "unspecified"))
      (node (ref "FRG") (pin "2") (pinfunction "2_2") (pintype "input"))
      (node (ref "H5") (pin "12") (pinfunction "12_12") (pintype "unspecified"))
      (node (ref "J2") (pin "12") (pinfunction "D9/0C1_12") (pintype "unspecified"))
      (node (ref "OUT_9") (pin "1") (pinfunction "1_1") (pintype "unspecified"))
    )
    (net (code "27") (name "D10") (class "Default")
      (node (ref "GLD") (pin "1") (pinfunction "A_1") (pintype "input"))
      (node (ref "GQ") (pin "1") (pinfunction "G_1") (pintype "unspecified"))
      (node (ref "GRG") (pin "2") (pinfunction "2_2") (pintype "input"))
      (node (ref "H5") (pin "13") (pinfunction "13_13") (pintype "unspecified"))
      (node (ref "J2") (pin "13") (pinfunction "D10_13") (pintype "unspecified"))
      (node (ref "OUT_10") (pin "1") (pinfunction "1_1") (pintype "unspecified"))
    )
    (net (code "28") (name "D11") (class "Default")
      (node (ref "H5") (pin "14") (pinfunction "14_14") (pintype "unspecified"))
      (node (ref "HLD") (pin "1") (pinfunction "A_1") (pintype "input"))
      (node (ref "HQ") (pin "1") (pinfunction "G_1") (pintype "unspecified"))
      (node (ref "HRG") (pin "2") (pinfunction "2_2") (pintype "input"))
      (node (ref "J2") (pin "14") (pinfunction "D11/MOSI_14") (pintype "unspecified"))
      (node (ref "OUT_11") (pin "1") (pinfunction "1_1") (pintype "unspecified"))
    )
    (net (code "29") (name "D13") (class "Default")
      (node (ref "H4") (pin "15") (pinfunction "15_15") (pintype "unspecified"))
      (node (ref "J2") (pin "16") (pinfunction "SCK/D13_16") (pintype "unspecified"))
    )
    (net (code "30") (name "GND") (class "Default")
      (node (ref "AQ") (pin "2") (pinfunction "S_2") (pintype "unspecified"))
      (node (ref "ARG") (pin "1") (pinfunction "1_1") (pintype "input"))
      (node (ref "ARL") (pin "1") (pinfunction "1_1") (pintype "input"))
      (node (ref "BQ") (pin "2") (pinfunction "S_2") (pintype "unspecified"))
      (node (ref "BRG") (pin "1") (pinfunction "1_1") (pintype "input"))
      (node (ref "BRL") (pin "1") (pinfunction "1_1") (pintype "input"))
      (node (ref "BUZZER1") (pin "2") (pinfunction "2_2") (pintype "unspecified"))
      (node (ref "C1") (pin "2") (pinfunction "2_2") (pintype "input"))
      (node (ref "C10") (pin "1") (pinfunction "1_1") (pintype "unspecified"))
      (node (ref "C11") (pin "1") (pinfunction "1_1") (pintype "unspecified"))
      (node (ref "C2") (pin "2") (pinfunction "2_2") (pintype "input"))
      (node (ref "CQ") (pin "2") (pinfunction "S_2") (pintype "unspecified"))
      (node (ref "CRG") (pin "1") (pinfunction "1_1") (pintype "input"))
      (node (ref "CRL") (pin "1") (pinfunction "1_1") (pintype "input"))
      (node (ref "DC1") (pin "2") (pinfunction "2_2") (pintype "unspecified"))
      (node (ref "DC1") (pin "3") (pinfunction "3_3") (pintype "unspecified"))
      (node (ref "DQ") (pin "2") (pinfunction "S_2") (pintype "unspecified"))
      (node (ref "DRG") (pin "1") (pinfunction "1_1") (pintype "input"))
      (node (ref "DRL") (pin "1") (pinfunction "1_1") (pintype "input"))
      (node (ref "EQ") (pin "2") (pinfunction "S_2") (pintype "unspecified"))
      (node (ref "ERG") (pin "1") (pinfunction "1_1") (pintype "input"))
      (node (ref "ERL") (pin "1") (pinfunction "1_1") (pintype "input"))
      (node (ref "EX_V") (pin "2") (pinfunction "2_2") (pintype "unspecified"))
      (node (ref "FQ") (pin "2") (pinfunction "S_2") (pintype "unspecified"))
      (node (ref "FRG") (pin "1") (pinfunction "1_1") (pintype "input"))
      (node (ref "FRL") (pin "1") (pinfunction "1_1") (pintype "input"))
      (node (ref "GQ") (pin "2") (pinfunction "S_2") (pintype "unspecified"))
      (node (ref "GRG") (pin "1") (pinfunction "1_1") (pintype "input"))
      (node (ref "GRL") (pin "1") (pinfunction "1_1") (pintype "input"))
      (node (ref "H1") (pin "6") (pinfunction "6_6") (pintype "input"))
      (node (ref "H11") (pin "6") (pinfunction "6_6") (pintype "input"))
      (node (ref "H2") (pin "6") (pinfunction "6_6") (pintype "input"))
      (node (ref "H3") (pin "6") (pinfunction "6_6") (pintype "input"))
      (node (ref "H4") (pin "2") (pinfunction "2_2") (pintype "unspecified"))
      (node (ref "H5") (pin "4") (pinfunction "4_4") (pintype "unspecified"))
      (node (ref "H6") (pin "6") (pinfunction "6_6") (pintype "input"))
      (node (ref "HQ") (pin "2") (pinfunction "S_2") (pintype "unspecified"))
      (node (ref "HRG") (pin "1") (pinfunction "1_1") (pintype "input"))
      (node (ref "HRL") (pin "1") (pinfunction "1_1") (pintype "input"))
      (node (ref "J2") (pin "29") (pinfunction "GND_29") (pintype "unspecified"))
      (node (ref "J2") (pin "4") (pinfunction "GND_4") (pintype "unspecified"))
      (node (ref "OLED") (pin "2") (pinfunction "GND_2") (pintype "passive"))
      (node (ref "OUT_10") (pin "2") (pinfunction "2_2") (pintype "unspecified"))
      (node (ref "OUT_11") (pin "2") (pinfunction "2_2") (pintype "unspecified"))
      (node (ref "OUT_4") (pin "2") (pinfunction "2_2") (pintype "unspecified"))
      (node (ref "OUT_5") (pin "2") (pinfunction "2_2") (pintype "unspecified"))
      (node (ref "OUT_6") (pin "2") (pinfunction "2_2") (pintype "unspecified"))
      (node (ref "OUT_7") (pin "2") (pinfunction "2_2") (pintype "unspecified"))
      (node (ref "OUT_8") (pin "2") (pinfunction "2_2") (pintype "unspecified"))
      (node (ref "OUT_9") (pin "2") (pinfunction "2_2") (pintype "unspecified"))
      (node (ref "P2") (pin "1") (pinfunction "1_1") (pintype "input"))
      (node (ref "P3") (pin "1") (pinfunction "1_1") (pintype "input"))
      (node (ref "RL12V") (pin "2") (pinfunction "2_2") (pintype "input"))
      (node (ref "RL5VB") (pin "2") (pinfunction "2_2") (pintype "input"))
      (node (ref "SENS_2") (pin "3") (pinfunction "3_3") (pintype "unspecified"))
      (node (ref "SENS_3") (pin "3") (pinfunction "3_3") (pintype "unspecified"))
      (node (ref "SENS_A0") (pin "3") (pinfunction "3_3") (pintype "unspecified"))
      (node (ref "SENS_A1") (pin "3") (pinfunction "3_3") (pintype "unspecified"))
      (node (ref "SENS_A2") (pin "3") (pinfunction "3_3") (pintype "unspecified"))
      (node (ref "SENS_A3") (pin "3") (pinfunction "3_3") (pintype "unspecified"))
      (node (ref "SW2") (pin "3") (pinfunction "3_3") (pintype "unspecified"))
      (node (ref "SW2") (pin "4") (pinfunction "4_4") (pintype "unspecified"))
      (node (ref "SW3") (pin "3") (pinfunction "3_3") (pintype "unspecified"))
      (node (ref "SW3") (pin "4") (pinfunction "4_4") (pintype "unspecified"))
      (node (ref "SWA0") (pin "3") (pinfunction "3_3") (pintype "unspecified"))
      (node (ref "SWA0") (pin "4") (pinfunction "4_4") (pintype "unspecified"))
      (node (ref "SWA1") (pin "3") (pinfunction "3_3") (pintype "unspecified"))
      (node (ref "SWA1") (pin "4") (pinfunction "4_4") (pintype "unspecified"))
      (node (ref "SWA2") (pin "3") (pinfunction "3_3") (pintype "unspecified"))
      (node (ref "SWA2") (pin "4") (pinfunction "4_4") (pintype "unspecified"))
      (node (ref "SWA3") (pin "3") (pinfunction "3_3") (pintype "unspecified"))
      (node (ref "SWA3") (pin "4") (pinfunction "4_4") (pintype "unspecified"))
      (node (ref "U3") (pin "3") (pinfunction "GND_3") (pintype "unspecified"))
      (node (ref "U5") (pin "2") (pinfunction "GND_2") (pintype "unspecified"))
      (node (ref "U6") (pin "1") (pinfunction "A1_1") (pintype "unspecified"))
      (node (ref "U6") (pin "2") (pinfunction "A0_2") (pintype "unspecified"))
      (node (ref "U6") (pin "7") (pinfunction "GND_7") (pintype "unspecified"))
    )
    (net (code "31") (name "Net-(ADM-A)") (class "Default")
      (node (ref "ACM") (pin "2") (pinfunction "2_2") (pintype "input"))
      (node (ref "ACON") (pin "2") (pinfunction "2_2") (pintype "unspecified"))
      (node (ref "ADM") (pin "2") (pinfunction "A_2") (pintype "unspecified"))
      (node (ref "AQ") (pin "3") (pinfunction "D_3") (pintype "unspecified"))
    )
    (net (code "32") (name "Net-(ADM-C)") (class "Default")
      (node (ref "ACM") (pin "1") (pinfunction "1_1") (pintype "input"))
      (node (ref "ACON") (pin "1") (pinfunction "1_1") (pintype "unspecified"))
      (node (ref "ADM") (pin "1") (pinfunction "C_1") (pintype "unspecified"))
      (node (ref "AJ12V") (pin "1") (pinfunction "1_1") (pintype "bidirectional"))
      (node (ref "AJ5V") (pin "1") (pinfunction "1_1") (pintype "bidirectional"))
    )
    (net (code "33") (name "Net-(ALD-C)") (class "Default")
      (node (ref "ALD") (pin "2") (pinfunction "C_2") (pintype "input"))
      (node (ref "ARL") (pin "2") (pinfunction "2_2") (pintype "input"))
    )
    (net (code "34") (name "Net-(BDM-A)") (class "Default")
      (node (ref "BCM") (pin "2") (pinfunction "2_2") (pintype "input"))
      (node (ref "BCON") (pin "2") (pinfunction "2_2") (pintype "unspecified"))
      (node (ref "BDM") (pin "2") (pinfunction "A_2") (pintype "unspecified"))
      (node (ref "BQ") (pin "3") (pinfunction "D_3") (pintype "unspecified"))
    )
    (net (code "35") (name "Net-(BDM-C)") (class "Default")
      (node (ref "BCM") (pin "1") (pinfunction "1_1") (pintype "input"))
      (node (ref "BCON") (pin "1") (pinfunction "1_1") (pintype "unspecified"))
      (node (ref "BDM") (pin "1") (pinfunction "C_1") (pintype "unspecified"))
      (node (ref "BJ12V") (pin "1") (pinfunction "1_1") (pintype "bidirectional"))
      (node (ref "BJ5V") (pin "1") (pinfunction "1_1") (pintype "bidirectional"))
    )
    (net (code "36") (name "Net-(BLD-C)") (class "Default")
      (node (ref "BLD") (pin "2") (pinfunction "C_2") (pintype "input"))
      (node (ref "BRL") (pin "2") (pinfunction "2_2") (pintype "input"))
    )
    (net (code "37") (name "Net-(CDM-A)") (class "Default")
      (node (ref "CCM") (pin "2") (pinfunction "2_2") (pintype "input"))
      (node (ref "CCON") (pin "2") (pinfunction "2_2") (pintype "unspecified"))
      (node (ref "CDM") (pin "2") (pinfunction "A_2") (pintype "unspecified"))
      (node (ref "CQ") (pin "3") (pinfunction "D_3") (pintype "unspecified"))
    )
    (net (code "38") (name "Net-(CDM-C)") (class "Default")
      (node (ref "CCM") (pin "1") (pinfunction "1_1") (pintype "input"))
      (node (ref "CCON") (pin "1") (pinfunction "1_1") (pintype "unspecified"))
      (node (ref "CDM") (pin "1") (pinfunction "C_1") (pintype "unspecified"))
      (node (ref "CJ12V") (pin "1") (pinfunction "1_1") (pintype "bidirectional"))
      (node (ref "CJ5V") (pin "1") (pinfunction "1_1") (pintype "bidirectional"))
    )
    (net (code "39") (name "Net-(CLD-C)") (class "Default")
      (node (ref "CLD") (pin "2") (pinfunction "C_2") (pintype "input"))
      (node (ref "CRL") (pin "2") (pinfunction "2_2") (pintype "input"))
    )
    (net (code "40") (name "Net-(D7-A)") (class "Default")
      (node (ref "D7") (pin "2") (pinfunction "A_2") (pintype "unspecified"))
      (node (ref "RLY4") (pin "4") (pinfunction "4_4") (pintype "unspecified"))
    )
    (net (code "41") (name "Net-(DDM-A)") (class "Default")
      (node (ref "DCM") (pin "2") (pinfunction "2_2") (pintype "input"))
      (node (ref "DCON") (pin "2") (pinfunction "2_2") (pintype "unspecified"))
      (node (ref "DDM") (pin "2") (pinfunction "A_2") (pintype "unspecified"))
      (node (ref "DQ") (pin "3") (pinfunction "D_3") (pintype "unspecified"))
    )
    (net (code "42") (name "Net-(DDM-C)") (class "Default")
      (node (ref "DCM") (pin "1") (pinfunction "1_1") (pintype "input"))
      (node (ref "DCON") (pin "1") (pinfunction "1_1") (pintype "unspecified"))
      (node (ref "DDM") (pin "1") (pinfunction "C_1") (pintype "unspecified"))
      (node (ref "DJ12V") (pin "1") (pinfunction "1_1") (pintype "bidirectional"))
      (node (ref "DJ5V") (pin "1") (pinfunction "1_1") (pintype "bidirectional"))
    )
    (net (code "43") (name "Net-(DDM1-A)") (class "Default")
      (node (ref "DDM1") (pin "2") (pinfunction "A_2") (pintype "unspecified"))
      (node (ref "VALVE-CON") (pin "2") (pinfunction "2_2") (pintype "unspecified"))
    )
    (net (code "44") (name "Net-(DDM1-C)") (class "Default")
      (node (ref "DDM1") (pin "1") (pinfunction "C_1") (pintype "unspecified"))
      (node (ref "RLY4") (pin "2") (pinfunction "2_2") (pintype "unspecified"))
      (node (ref "VALVE-CON") (pin "1") (pinfunction "1_1") (pintype "unspecified"))
    )
    (net (code "45") (name "Net-(DDM2-A)") (class "Default")
      (node (ref "DDM2") (pin "2") (pinfunction "A_2") (pintype "unspecified"))
      (node (ref "IGNIT_CON") (pin "2") (pinfunction "2_2") (pintype "unspecified"))
    )
    (net (code "46") (name "Net-(DDM2-C)") (class "Default")
      (node (ref "DDM2") (pin "1") (pinfunction "C_1") (pintype "unspecified"))
      (node (ref "IGNIT_CON") (pin "1") (pinfunction "1_1") (pintype "unspecified"))
      (node (ref "RLY4") (pin "1") (pinfunction "1_1") (pintype "unspecified"))
    )
    (net (code "47") (name "Net-(DLD-C)") (class "Default")
      (node (ref "DLD") (pin "2") (pinfunction "C_2") (pintype "input"))
      (node (ref "DRL") (pin "2") (pinfunction "2_2") (pintype "input"))
    )
    (net (code "48") (name "Net-(EDM-A)") (class "Default")
      (node (ref "ECM") (pin "2") (pinfunction "2_2") (pintype "input"))
      (node (ref "ECON") (pin "2") (pinfunction "2_2") (pintype "unspecified"))
      (node (ref "EDM") (pin "2") (pinfunction "A_2") (pintype "unspecified"))
      (node (ref "EQ") (pin "3") (pinfunction "D_3") (pintype "unspecified"))
    )
    (net (code "49") (name "Net-(EDM-C)") (class "Default")
      (node (ref "ECM") (pin "1") (pinfunction "1_1") (pintype "input"))
      (node (ref "ECON") (pin "1") (pinfunction "1_1") (pintype "unspecified"))
      (node (ref "EDM") (pin "1") (pinfunction "C_1") (pintype "unspecified"))
      (node (ref "EJ12V") (pin "1") (pinfunction "1_1") (pintype "bidirectional"))
      (node (ref "EJ5V") (pin "1") (pinfunction "1_1") (pintype "bidirectional"))
    )
    (net (code "50") (name "Net-(ELD-C)") (class "Default")
      (node (ref "ELD") (pin "2") (pinfunction "C_2") (pintype "input"))
      (node (ref "ERL") (pin "2") (pinfunction "2_2") (pintype "input"))
    )
    (net (code "51") (name "Net-(FDM-A)") (class "Default")
      (node (ref "FCM") (pin "2") (pinfunction "2_2") (pintype "input"))
      (node (ref "FCON") (pin "2") (pinfunction "2_2") (pintype "unspecified"))
      (node (ref "FDM") (pin "2") (pinfunction "A_2") (pintype "unspecified"))
      (node (ref "FQ") (pin "3") (pinfunction "D_3") (pintype "unspecified"))
    )
    (net (code "52") (name "Net-(FDM-C)") (class "Default")
      (node (ref "FCM") (pin "1") (pinfunction "1_1") (pintype "input"))
      (node (ref "FCON") (pin "1") (pinfunction "1_1") (pintype "unspecified"))
      (node (ref "FDM") (pin "1") (pinfunction "C_1") (pintype "unspecified"))
      (node (ref "FJ12V") (pin "1") (pinfunction "1_1") (pintype "bidirectional"))
      (node (ref "FJ5V") (pin "1") (pinfunction "1_1") (pintype "bidirectional"))
    )
    (net (code "53") (name "Net-(FLD-C)") (class "Default")
      (node (ref "FLD") (pin "2") (pinfunction "C_2") (pintype "input"))
      (node (ref "FRL") (pin "2") (pinfunction "2_2") (pintype "input"))
    )
    (net (code "54") (name "Net-(GDM-A)") (class "Default")
      (node (ref "GCM") (pin "2") (pinfunction "2_2") (pintype "input"))
      (node (ref "GCON") (pin "2") (pinfunction "2_2") (pintype "unspecified"))
      (node (ref "GDM") (pin "2") (pinfunction "A_2") (pintype "unspecified"))
      (node (ref "GQ") (pin "3") (pinfunction "D_3") (pintype "unspecified"))
    )
    (net (code "55") (name "Net-(GDM-C)") (class "Default")
      (node (ref "GCM") (pin "1") (pinfunction "1_1") (pintype "input"))
      (node (ref "GCON") (pin "1") (pinfunction "1_1") (pintype "unspecified"))
      (node (ref "GDM") (pin "1") (pinfunction "C_1") (pintype "unspecified"))
      (node (ref "GJ12V") (pin "1") (pinfunction "1_1") (pintype "bidirectional"))
      (node (ref "GJ5V") (pin "1") (pinfunction "1_1") (pintype "bidirectional"))
    )
    (net (code "56") (name "Net-(GLD-C)") (class "Default")
      (node (ref "GLD") (pin "2") (pinfunction "C_2") (pintype "input"))
      (node (ref "GRL") (pin "2") (pinfunction "2_2") (pintype "input"))
    )
    (net (code "57") (name "Net-(H4-Pad3)") (class "Default")
      (node (ref "H4") (pin "3") (pinfunction "3_3") (pintype "unspecified"))
      (node (ref "J2") (pin "28") (pinfunction "RESET_28") (pintype "unspecified"))
    )
    (net (code "58") (name "Net-(H5-Pad3)") (class "Default")
      (node (ref "H5") (pin "3") (pinfunction "3_3") (pintype "unspecified"))
      (node (ref "J2") (pin "3") (pinfunction "RESET_3") (pintype "unspecified"))
    )
    (net (code "59") (name "Net-(HDM-A)") (class "Default")
      (node (ref "HCM") (pin "2") (pinfunction "2_2") (pintype "input"))
      (node (ref "HCON") (pin "2") (pinfunction "2_2") (pintype "unspecified"))
      (node (ref "HDM") (pin "2") (pinfunction "A_2") (pintype "unspecified"))
      (node (ref "HQ") (pin "3") (pinfunction "D_3") (pintype "unspecified"))
    )
    (net (code "60") (name "Net-(HDM-C)") (class "Default")
      (node (ref "HCM") (pin "1") (pinfunction "1_1") (pintype "input"))
      (node (ref "HCON") (pin "1") (pinfunction "1_1") (pintype "unspecified"))
      (node (ref "HDM") (pin "1") (pinfunction "C_1") (pintype "unspecified"))
      (node (ref "HJ12V") (pin "1") (pinfunction "1_1") (pintype "bidirectional"))
      (node (ref "HJ5V") (pin "1") (pinfunction "1_1") (pintype "bidirectional"))
    )
    (net (code "61") (name "Net-(HLD-C)") (class "Default")
      (node (ref "HLD") (pin "2") (pinfunction "C_2") (pintype "input"))
      (node (ref "HRL") (pin "2") (pinfunction "2_2") (pintype "input"))
    )
    (net (code "62") (name "Net-(J2-AREF)") (class "Default")
      (node (ref "H4") (pin "13") (pinfunction "13_13") (pintype "unspecified"))
      (node (ref "J2") (pin "18") (pinfunction "AREF_18") (pintype "unspecified"))
    )
    (net (code "63") (name "Net-(L12V-C)") (class "Default")
      (node (ref "L12V") (pin "2") (pinfunction "C_2") (pintype "input"))
      (node (ref "RL12V") (pin "1") (pinfunction "1_1") (pintype "input"))
    )
    (net (code "64") (name "Net-(LVB-C)") (class "Default")
      (node (ref "LVB") (pin "2") (pinfunction "C_2") (pintype "input"))
      (node (ref "RL5VB") (pin "1") (pinfunction "1_1") (pintype "input"))
    )
    (net (code "65") (name "Net-(U3-EN)") (class "Default")
      (node (ref "R1") (pin "1") (pinfunction "1_1") (pintype "input"))
      (node (ref "U3") (pin "1") (pinfunction "EN_1") (pintype "unspecified"))
    )
    (net (code "67") (name "unconnected-(H1-Pad2)") (class "Default")
      (node (ref "H1") (pin "2") (pinfunction "2_2") (pintype "input"))
    )
    (net (code "68") (name "unconnected-(H1-Pad3)") (class "Default")
      (node (ref "H1") (pin "3") (pinfunction "3_3") (pintype "input"))
    )
    (net (code "69") (name "unconnected-(H1-Pad4)") (class "Default")
      (node (ref "H1") (pin "4") (pinfunction "4_4") (pintype "input"))
    )
    (net (code "70") (name "unconnected-(H1-Pad5)") (class "Default")
      (node (ref "H1") (pin "5") (pinfunction "5_5") (pintype "input"))
    )
    (net (code "71") (name "unconnected-(H2-Pad2)") (class "Default")
      (node (ref "H2") (pin "2") (pinfunction "2_2") (pintype "input"))
    )
    (net (code "72") (name "unconnected-(H2-Pad3)") (class "Default")
      (node (ref "H2") (pin "3") (pinfunction "3_3") (pintype "input"))
    )
    (net (code "73") (name "unconnected-(H2-Pad4)") (class "Default")
      (node (ref "H2") (pin "4") (pinfunction "4_4") (pintype "input"))
    )
    (net (code "74") (name "unconnected-(H2-Pad5)") (class "Default")
      (node (ref "H2") (pin "5") (pinfunction "5_5") (pintype "input"))
    )
    (net (code "75") (name "unconnected-(H3-Pad2)") (class "Default")
      (node (ref "H3") (pin "2") (pinfunction "2_2") (pintype "input"))
    )
    (net (code "76") (name "unconnected-(H3-Pad3)") (class "Default")
      (node (ref "H3") (pin "3") (pinfunction "3_3") (pintype "input"))
    )
    (net (code "77") (name "unconnected-(H3-Pad4)") (class "Default")
      (node (ref "H3") (pin "4") (pinfunction "4_4") (pintype "input"))
    )
    (net (code "78") (name "unconnected-(H3-Pad5)") (class "Default")
      (node (ref "H3") (pin "5") (pinfunction "5_5") (pintype "input"))
    )
    (net (code "79") (name "unconnected-(H6-Pad2)") (class "Default")
      (node (ref "H6") (pin "2") (pinfunction "2_2") (pintype "input"))
    )
    (net (code "80") (name "unconnected-(H6-Pad3)") (class "Default")
      (node (ref "H6") (pin "3") (pinfunction "3_3") (pintype "input"))
    )
    (net (code "81") (name "unconnected-(H6-Pad4)") (class "Default")
      (node (ref "H6") (pin "4") (pinfunction "4_4") (pintype "input"))
    )
    (net (code "82") (name "unconnected-(H6-Pad5)") (class "Default")
      (node (ref "H6") (pin "5") (pinfunction "5_5") (pintype "input"))
    )
    (net (code "83") (name "unconnected-(H11-Pad2)") (class "Default")
      (node (ref "H11") (pin "2") (pinfunction "2_2") (pintype "input"))
    )
    (net (code "84") (name "unconnected-(H11-Pad3)") (class "Default")
      (node (ref "H11") (pin "3") (pinfunction "3_3") (pintype "input"))
    )
    (net (code "85") (name "unconnected-(H11-Pad4)") (class "Default")
      (node (ref "H11") (pin "4") (pinfunction "4_4") (pintype "input"))
    )
    (net (code "86") (name "unconnected-(H11-Pad5)") (class "Default")
      (node (ref "H11") (pin "5") (pinfunction "5_5") (pintype "input"))
    )
    (net (code "87") (name "unconnected-(P2-Pad4)") (class "Default")
      (node (ref "P2") (pin "4") (pinfunction "4_4") (pintype "input"))
    )
    (net (code "88") (name "unconnected-(P2-Pad5)") (class "Default")
      (node (ref "P2") (pin "5") (pinfunction "5_5") (pintype "input"))
    )
    (net (code "89") (name "unconnected-(P3-Pad4)") (class "Default")
      (node (ref "P3") (pin "4") (pinfunction "4_4") (pintype "input"))
    )
    (net (code "90") (name "unconnected-(P3-Pad5)") (class "Default")
      (node (ref "P3") (pin "5") (pinfunction "5_5") (pintype "input"))
    )
    (net (code "91") (name "unconnected-(R2-Pad1)") (class "Default")
      (node (ref "R2") (pin "1") (pinfunction "1_1") (pintype "unspecified"))
    )
    (net (code "92") (name "unconnected-(R2-Pad2)") (class "Default")
      (node (ref "R2") (pin "2") (pinfunction "2_2") (pintype "unspecified"))
    )
    (net (code "93") (name "unconnected-(U1-Pad1)") (class "Default")
      (node (ref "U1") (pin "1") (pinfunction "1_1") (pintype "unspecified"))
    )
    (net (code "94") (name "unconnected-(U1-Pad2)") (class "Default")
      (node (ref "U1") (pin "2") (pinfunction "2_2") (pintype "unspecified"))
    )
    (net (code "95") (name "unconnected-(U1-Pad3)") (class "Default")
      (node (ref "U1") (pin "3") (pinfunction "3_3") (pintype "unspecified"))
    )
    (net (code "96") (name "unconnected-(U1-Pad4)") (class "Default")
      (node (ref "U1") (pin "4") (pinfunction "4_4") (pintype "unspecified"))
    )
    (net (code "97") (name "unconnected-(U2-A0-Pad2)") (class "Default")
      (node (ref "U2") (pin "2") (pinfunction "A0_2") (pintype "unspecified"))
    )
    (net (code "98") (name "unconnected-(U2-A1-Pad1)") (class "Default")
      (node (ref "U2") (pin "1") (pinfunction "A1_1") (pintype "unspecified"))
    )
    (net (code "99") (name "unconnected-(U2-Alert-Pad3)") (class "Default")
      (node (ref "U2") (pin "3") (pinfunction "Alert_3") (pintype "unspecified"))
    )
    (net (code "100") (name "unconnected-(U2-GND-Pad7)") (class "Default")
      (node (ref "U2") (pin "7") (pinfunction "GND_7") (pintype "unspecified"))
    )
    (net (code "101") (name "unconnected-(U2-SCL-Pad5)") (class "Default")
      (node (ref "U2") (pin "5") (pinfunction "SCL_5") (pintype "unspecified"))
    )
    (net (code "102") (name "unconnected-(U2-SDA-Pad4)") (class "Default")
      (node (ref "U2") (pin "4") (pinfunction "SDA_4") (pintype "unspecified"))
    )
    (net (code "103") (name "unconnected-(U2-VBUS-Pad8)") (class "Default")
      (node (ref "U2") (pin "8") (pinfunction "VBUS_8") (pintype "unspecified"))
    )
    (net (code "104") (name "unconnected-(U2-VIN+-Pad10)") (class "Default")
      (node (ref "U2") (pin "10") (pinfunction "VIN+_10") (pintype "unspecified"))
    )
    (net (code "105") (name "unconnected-(U2-VIN--Pad9)") (class "Default")
      (node (ref "U2") (pin "9") (pinfunction "VIN-_9") (pintype "unspecified"))
    )
    (net (code "106") (name "unconnected-(U2-VS+-Pad6)") (class "Default")
      (node (ref "U2") (pin "6") (pinfunction "VS+_6") (pintype "unspecified"))
    )
    (net (code "107") (name "unconnected-(U4-Pad1)") (class "Default")
      (node (ref "U4") (pin "1") (pinfunction "1_1") (pintype "unspecified"))
    )
    (net (code "108") (name "unconnected-(U4-Pad2)") (class "Default")
      (node (ref "U4") (pin "2") (pinfunction "2_2") (pintype "unspecified"))
    )
    (net (code "109") (name "unconnected-(U6-Alert-Pad3)") (class "Default")
      (node (ref "U6") (pin "3") (pinfunction "Alert_3") (pintype "unspecified"))
    )
    (net (code "110") (name "unconnected-(U6-VBUS-Pad8)") (class "Default")
      (node (ref "U6") (pin "8") (pinfunction "VBUS_8") (pintype "unspecified"))
    )
    (net (code "111") (name "unconnected-(U6-VIN+-Pad10)") (class "Default")
      (node (ref "U6") (pin "10") (pinfunction "VIN+_10") (pintype "unspecified"))
    )
    (net (code "112") (name "unconnected-(U6-VIN--Pad9)") (class "Default")
      (node (ref "U6") (pin "9") (pinfunction "VIN-_9") (pintype "unspecified"))
    )
  )
)
